# Procesador_3.net
KiCad netlist of a schematic drawn in Altium Designer
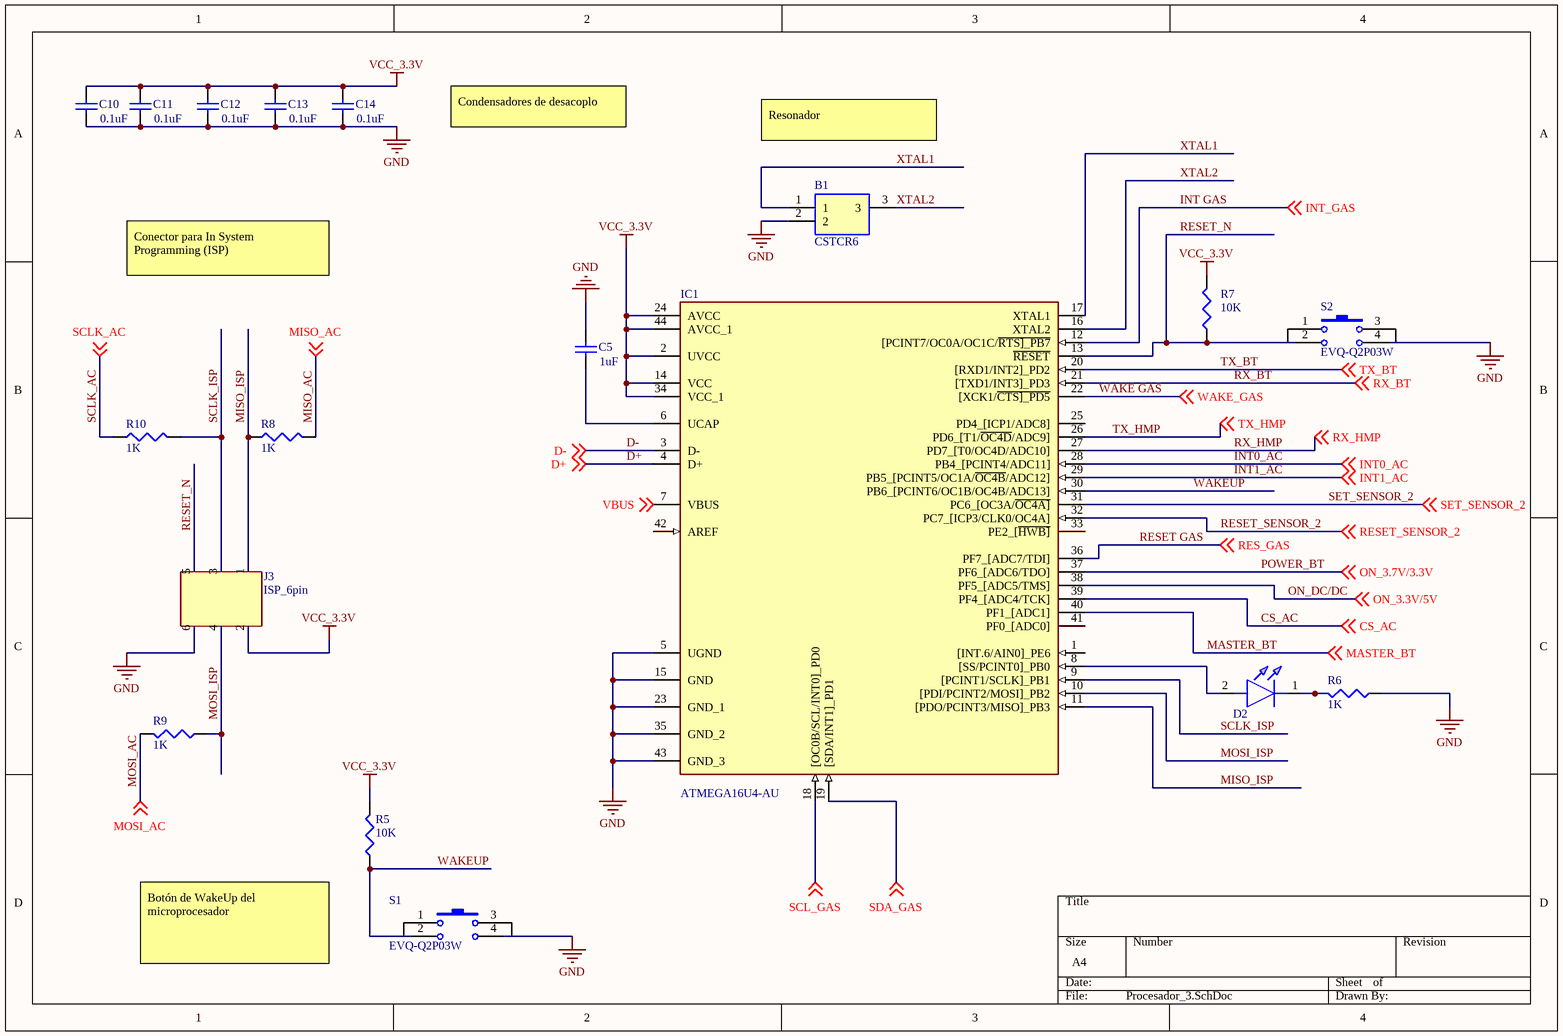
[diagram p0: Procesador_3.SchDoc]

(export (version "E")
  (design (tool "Eeschema 10.0.6"))
  (components
    (comp (ref "B1")
      (value "CSTCR6")
      (footprint "CSTCR6M00G53")
      (fields
        (field (name "MOUSER PART NUMBER") "81-CSTCE16M0V53C-R0")
        (field (name "MANUFACTURER_PART_NUMBER") "CSTCE16M0V53C-R0")
      )
      (libsource (lib "Bicimaps") (part "CSTCE16M0V53C-R0"))
    )
    (comp (ref "C5")
      (value "1uF")
      (footprint "0603")
      (description "Capacitor")
      (fields (field (name "Comment") "Cap") (field (name "PUBLISHER") "Altium Limited"))
      (libsource (lib "Bicimaps") (part "Cap_0603"))
    )
    (comp (ref "C10")
      (value "0.1uF")
      (footprint "0603")
      (description "Capacitor")
      (fields (field (name "Comment") "Cap") (field (name "PUBLISHER") "Altium Limited"))
      (libsource (lib "Bicimaps") (part "Cap_0603"))
    )
    (comp (ref "C11")
      (value "0.1uF")
      (footprint "0603")
      (description "Capacitor")
      (fields (field (name "Comment") "Cap") (field (name "PUBLISHER") "Altium Limited"))
      (libsource (lib "Bicimaps") (part "Cap_0603"))
    )
    (comp (ref "C12")
      (value "0.1uF")
      (footprint "0603")
      (description "Capacitor")
      (fields (field (name "Comment") "Cap") (field (name "PUBLISHER") "Altium Limited"))
      (libsource (lib "Bicimaps") (part "Cap_0603"))
    )
    (comp (ref "C13")
      (value "0.1uF")
      (footprint "0603")
      (description "Capacitor")
      (fields (field (name "Comment") "Cap") (field (name "PUBLISHER") "Altium Limited"))
      (libsource (lib "Bicimaps") (part "Cap_0603"))
    )
    (comp (ref "C14")
      (value "0.1uF")
      (footprint "0603")
      (description "Capacitor")
      (fields (field (name "Comment") "Cap") (field (name "PUBLISHER") "Altium Limited"))
      (libsource (lib "Bicimaps") (part "Cap_0603"))
    )
    (comp (ref "D2")
      (value "150060GS75000")
      (footprint "LEDC1608X80N")
      (description "Wurth Elektronik WL-SMCW 520 nm Green LED, 1608 (0603) Clear SMD package")
      (fields (field (name "RS PART NUMBER") "8154209P"))
      (libsource (lib "Bicimaps") (part "150060GS75000"))
    )
    (comp (ref "IC1")
      (value "ATMEGA16U4-AU")
      (footprint "ATMEGA 16U4")
      (description "Integrated Circuit")
      (libsource (lib "BiciMaps_2") (part "ATMEGA16U4-AU"))
    )
    (comp (ref "J3") (value "ISP_6pin") (footprint "ISP_6PIN") (libsource (lib "Bicimaps") (part "ISP_6pin")))
    (comp (ref "R5")
      (value "10K")
      (footprint "0603")
      (description "Resistor")
      (fields (field (name "Comment") "Res3") (field (name "PUBLISHER") "Altium Limited"))
      (libsource (lib "Miscellaneous Devices") (part "Res3"))
    )
    (comp (ref "R6")
      (value "1K")
      (footprint "0603")
      (description "Resistor")
      (fields (field (name "Comment") "Res3") (field (name "PUBLISHER") "Altium Limited"))
      (libsource (lib "Miscellaneous Devices") (part "Res3"))
    )
    (comp (ref "R7")
      (value "10K")
      (footprint "0603")
      (description "Resistor")
      (fields (field (name "Comment") "Res3") (field (name "PUBLISHER") "Altium Limited"))
      (libsource (lib "Miscellaneous Devices") (part "Res3"))
    )
    (comp (ref "R8")
      (value "1K")
      (footprint "0603")
      (description "Resistor")
      (fields (field (name "Comment") "Res3") (field (name "PUBLISHER") "Altium Limited"))
      (libsource (lib "Miscellaneous Devices") (part "Res3"))
    )
    (comp (ref "R9")
      (value "1K")
      (footprint "0603")
      (description "Resistor")
      (fields (field (name "Comment") "Res3") (field (name "PUBLISHER") "Altium Limited"))
      (libsource (lib "Miscellaneous Devices") (part "Res3"))
    )
    (comp (ref "R10")
      (value "1K")
      (footprint "0603")
      (description "Resistor")
      (fields (field (name "Comment") "Res3") (field (name "PUBLISHER") "Altium Limited"))
      (libsource (lib "Miscellaneous Devices") (part "Res3"))
    )
    (comp (ref "S1")
      (value "EVQ-Q2P03W")
      (footprint "EVQ-Q2P03W")
      (description "Tactile 3.1 heigth")
      (fields (field (name "MANUFACTURER_PART_NUMBER") "EVQP2602W"))
      (libsource (lib "Bicimaps") (part "EVQ-Q2P03W"))
    )
    (comp (ref "S2")
      (value "EVQ-Q2P03W")
      (footprint "EVQ-Q2P03W")
      (description "Tactile 3.1 heigth")
      (fields (field (name "MANUFACTURER_PART_NUMBER") "EVQP2602W"))
      (libsource (lib "Bicimaps") (part "EVQ-Q2P03W"))
    )
  )
  (nets
    (net (code "1") (name "/MISO_ISP") (class "Default")
      (node (ref "IC1") (pin "11") (pinfunction "[PDO/PCINT3/MISO]_PB3_11") (pintype "input"))
      (node (ref "J3") (pin "1") (pinfunction "1_1") (pintype "bidirectional"))
      (node (ref "R8") (pin "1") (pinfunction "1_1") (pintype "passive"))
    )
    (net (code "2") (name "/MOSI_ISP") (class "Default")
      (node (ref "IC1") (pin "10") (pinfunction "[PDI/PCINT2/MOSI]_PB2_10") (pintype "input"))
      (node (ref "J3") (pin "4") (pinfunction "4_4") (pintype "bidirectional"))
      (node (ref "R9") (pin "1") (pinfunction "1_1") (pintype "passive"))
    )
    (net (code "3") (name "/RESET_N") (class "Default")
      (node (ref "IC1") (pin "13") (pinfunction "~{RESET}_13") (pintype "passive"))
      (node (ref "J3") (pin "5") (pinfunction "5_5") (pintype "bidirectional"))
      (node (ref "R7") (pin "1") (pinfunction "1_1") (pintype "passive"))
      (node (ref "S2") (pin "2") (pinfunction "1_2") (pintype "passive"))
    )
    (net (code "4") (name "/SCLK_ISP") (class "Default")
      (node (ref "IC1") (pin "9") (pinfunction "[PCINT1/SCLK]_PB1_9") (pintype "input"))
      (node (ref "J3") (pin "3") (pinfunction "3_3") (pintype "bidirectional"))
      (node (ref "R10") (pin "2") (pinfunction "2_2") (pintype "passive"))
    )
    (net (code "5") (name "/WAKEUP") (class "Default")
      (node (ref "IC1") (pin "30") (pinfunction "PB6_[PCINT6/OC1B/OC4B/ADC13]_30") (pintype "input"))
      (node (ref "R5") (pin "1") (pinfunction "1_1") (pintype "passive"))
      (node (ref "S1") (pin "2") (pinfunction "1_2") (pintype "passive"))
    )
    (net (code "6") (name "/XTAL1") (class "Default")
      (node (ref "B1") (pin "1") (pinfunction "1_1") (pintype "passive"))
      (node (ref "IC1") (pin "17") (pinfunction "XTAL1_17") (pintype "passive"))
    )
    (net (code "7") (name "/XTAL2") (class "Default")
      (node (ref "B1") (pin "3") (pinfunction "3_3") (pintype "passive"))
      (node (ref "IC1") (pin "16") (pinfunction "XTAL2_16") (pintype "passive"))
    )
    (net (code "8") (name "CS_AC") (class "Default")
      (node (ref "IC1") (pin "39") (pinfunction "PF4_[ADC4/TCK]_39") (pintype "passive"))
    )
    (net (code "9") (name "D+") (class "Default")
      (node (ref "IC1") (pin "4") (pinfunction "D+_4") (pintype "passive"))
    )
    (net (code "10") (name "D-") (class "Default")
      (node (ref "IC1") (pin "3") (pinfunction "D-_3") (pintype "passive"))
    )
    (net (code "11") (name "GND") (class "Default")
      (node (ref "B1") (pin "2") (pinfunction "2_2") (pintype "power_in"))
      (node (ref "C10") (pin "1") (pinfunction "1_1") (pintype "passive"))
      (node (ref "C11") (pin "1") (pinfunction "1_1") (pintype "passive"))
      (node (ref "C12") (pin "1") (pinfunction "1_1") (pintype "passive"))
      (node (ref "C13") (pin "1") (pinfunction "1_1") (pintype "passive"))
      (node (ref "C14") (pin "1") (pinfunction "1_1") (pintype "passive"))
      (node (ref "C5") (pin "2") (pinfunction "2_2") (pintype "passive"))
      (node (ref "IC1") (pin "15") (pinfunction "GND_15") (pintype "power_in"))
      (node (ref "IC1") (pin "23") (pinfunction "GND_1_23") (pintype "power_in"))
      (node (ref "IC1") (pin "35") (pinfunction "GND_2_35") (pintype "power_in"))
      (node (ref "IC1") (pin "43") (pinfunction "GND_3_43") (pintype "power_in"))
      (node (ref "IC1") (pin "5") (pinfunction "UGND_5") (pintype "power_in"))
      (node (ref "J3") (pin "6") (pinfunction "6_6") (pintype "power_in"))
      (node (ref "R6") (pin "1") (pinfunction "1_1") (pintype "passive"))
      (node (ref "S1") (pin "4") (pinfunction "4_4") (pintype "passive"))
      (node (ref "S2") (pin "4") (pinfunction "4_4") (pintype "passive"))
    )
    (net (code "12") (name "INT0_AC") (class "Default")
      (node (ref "IC1") (pin "28") (pinfunction "PB4_[PCINT4/ADC11]_28") (pintype "input"))
    )
    (net (code "13") (name "INT1_AC") (class "Default")
      (node (ref "IC1") (pin "29") (pinfunction "PB5_[PCINT5/OC1A/~{OC4B}/ADC12]_29") (pintype "input"))
    )
    (net (code "14") (name "INT_GAS") (class "Default")
      (node (ref "IC1") (pin "12") (pinfunction "[PCINT7/OC0A/OC1C/~{RTS]_PB7}_12") (pintype "input"))
    )
    (net (code "15") (name "MASTER_BT") (class "Default")
      (node (ref "IC1") (pin "40") (pinfunction "PF1_[ADC1]_40") (pintype "passive"))
    )
    (net (code "16") (name "MISO_AC") (class "Default")
      (node (ref "R8") (pin "2") (pinfunction "2_2") (pintype "passive"))
    )
    (net (code "17") (name "MOSI_AC") (class "Default")
      (node (ref "R9") (pin "2") (pinfunction "2_2") (pintype "passive"))
    )
    (net (code "18") (name "Net-(D2-A)") (class "Default")
      (node (ref "D2") (pin "2") (pinfunction "A_2") (pintype "passive"))
      (node (ref "IC1") (pin "8") (pinfunction "[SS/PCINT0]_PB0_8") (pintype "input"))
    )
    (net (code "19") (name "Net-(D2-K)") (class "Default")
      (node (ref "D2") (pin "1") (pinfunction "K_1") (pintype "passive"))
      (node (ref "R6") (pin "2") (pinfunction "2_2") (pintype "passive"))
    )
    (net (code "20") (name "Net-(IC1-UCAP)") (class "Default")
      (node (ref "C5") (pin "1") (pinfunction "1_1") (pintype "passive"))
      (node (ref "IC1") (pin "6") (pinfunction "UCAP_6") (pintype "passive"))
    )
    (net (code "21") (name "ON_3.3V{slash}5V") (class "Default")
      (node (ref "IC1") (pin "38") (pinfunction "PF5_[ADC5/TMS]_38") (pintype "passive"))
    )
    (net (code "22") (name "ON_3.7V{slash}3.3V") (class "Default")
      (node (ref "IC1") (pin "37") (pinfunction "PF6_[ADC6/TDO]_37") (pintype "passive"))
    )
    (net (code "23") (name "RESET_SENSOR_2") (class "Default")
      (node (ref "IC1") (pin "32") (pinfunction "PC7_[ICP3/CLK0/OC4A]_32") (pintype "input"))
    )
    (net (code "24") (name "RES_GAS") (class "Default")
      (node (ref "IC1") (pin "36") (pinfunction "PF7_[ADC7/TDI]_36") (pintype "passive"))
    )
    (net (code "25") (name "RX_BT") (class "Default")
      (node (ref "IC1") (pin "21") (pinfunction "[TXD1/INT3]_PD3_21") (pintype "input"))
    )
    (net (code "26") (name "RX_HMP") (class "Default")
      (node (ref "IC1") (pin "27") (pinfunction "PD7_[T0/OC4D/ADC10]_27") (pintype "passive"))
    )
    (net (code "27") (name "SCLK_AC") (class "Default")
      (node (ref "R10") (pin "1") (pinfunction "1_1") (pintype "passive"))
    )
    (net (code "28") (name "SCL_GAS") (class "Default")
      (node (ref "IC1") (pin "18") (pinfunction "[OC0B/SCL/INT0]_PD0_18") (pintype "input"))
    )
    (net (code "29") (name "SDA_GAS") (class "Default")
      (node (ref "IC1") (pin "19") (pinfunction "[SDA/INT1]_PD1_19") (pintype "input"))
    )
    (net (code "30") (name "SET_SENSOR_2") (class "Default")
      (node (ref "IC1") (pin "31") (pinfunction "PC6_[OC3A/~{OC4A]}_31") (pintype "passive"))
    )
    (net (code "31") (name "TX_BT") (class "Default")
      (node (ref "IC1") (pin "20") (pinfunction "[RXD1/INT2]_PD2_20") (pintype "input"))
    )
    (net (code "32") (name "TX_HMP") (class "Default")
      (node (ref "IC1") (pin "26") (pinfunction "PD6_[T1/~{OC4D}/ADC9]_26") (pintype "passive"))
    )
    (net (code "33") (name "VBUS") (class "Default")
      (node (ref "IC1") (pin "7") (pinfunction "VBUS_7") (pintype "passive"))
    )
    (net (code "34") (name "VCC_3.3V") (class "Default")
      (node (ref "C10") (pin "2") (pinfunction "2_2") (pintype "passive"))
      (node (ref "C11") (pin "2") (pinfunction "2_2") (pintype "passive"))
      (node (ref "C12") (pin "2") (pinfunction "2_2") (pintype "passive"))
      (node (ref "C13") (pin "2") (pinfunction "2_2") (pintype "passive"))
      (node (ref "C14") (pin "2") (pinfunction "2_2") (pintype "passive"))
      (node (ref "IC1") (pin "14") (pinfunction "VCC_14") (pintype "power_in"))
      (node (ref "IC1") (pin "2") (pinfunction "UVCC_2") (pintype "power_in"))
      (node (ref "IC1") (pin "24") (pinfunction "AVCC_24") (pintype "power_in"))
      (node (ref "IC1") (pin "34") (pinfunction "VCC_1_34") (pintype "power_in"))
      (node (ref "IC1") (pin "44") (pinfunction "AVCC_1_44") (pintype "power_in"))
      (node (ref "J3") (pin "2") (pinfunction "2_2") (pintype "power_in"))
      (node (ref "R5") (pin "2") (pinfunction "2_2") (pintype "passive"))
      (node (ref "R7") (pin "2") (pinfunction "2_2") (pintype "passive"))
    )
    (net (code "35") (name "WAKE_GAS") (class "Default")
      (node (ref "IC1") (pin "22") (pinfunction "[XCK1/~{CTS]_PD5}_22") (pintype "passive"))
    )
    (net (code "36") (name "unconnected-(IC1-AREF-Pad42)") (class "Default")
      (node (ref "IC1") (pin "42") (pinfunction "AREF_42") (pintype "input"))
    )
    (net (code "37") (name "unconnected-(IC1-PD4_[ICP1{slash}ADC8]-Pad25)") (class "Default")
      (node (ref "IC1") (pin "25") (pinfunction "PD4_[ICP1/ADC8]_25") (pintype "passive"))
    )
    (net (code "38") (name "unconnected-(IC1-PE2_[~{HWB]}-Pad33)") (class "Default")
      (node (ref "IC1") (pin "33") (pinfunction "PE2_[~{HWB]}_33") (pintype "passive"))
    )
    (net (code "39") (name "unconnected-(IC1-PF0_[ADC0]-Pad41)") (class "Default")
      (node (ref "IC1") (pin "41") (pinfunction "PF0_[ADC0]_41") (pintype "passive"))
    )
    (net (code "40") (name "unconnected-(IC1-[INT.6{slash}AIN0]_PE6-Pad1)") (class "Default")
      (node (ref "IC1") (pin "1") (pinfunction "[INT.6/AIN0]_PE6_1") (pintype "input"))
    )
    (net (code "41") (name "unconnected-(S1-Pad1)") (class "Default")
      (node (ref "S1") (pin "1") (pinfunction "1_1") (pintype "passive"))
    )
    (net (code "42") (name "unconnected-(S1-Pad3)") (class "Default")
      (node (ref "S1") (pin "3") (pinfunction "3_3") (pintype "passive"))
    )
    (net (code "43") (name "unconnected-(S2-Pad1)") (class "Default")
      (node (ref "S2") (pin "1") (pinfunction "1_1") (pintype "passive"))
    )
    (net (code "44") (name "unconnected-(S2-Pad3)") (class "Default")
      (node (ref "S2") (pin "3") (pinfunction "3_3") (pintype "passive"))
    )
  )
)
